# Sequenzer.net
KiCad netlist of a schematic drawn in EAGLE
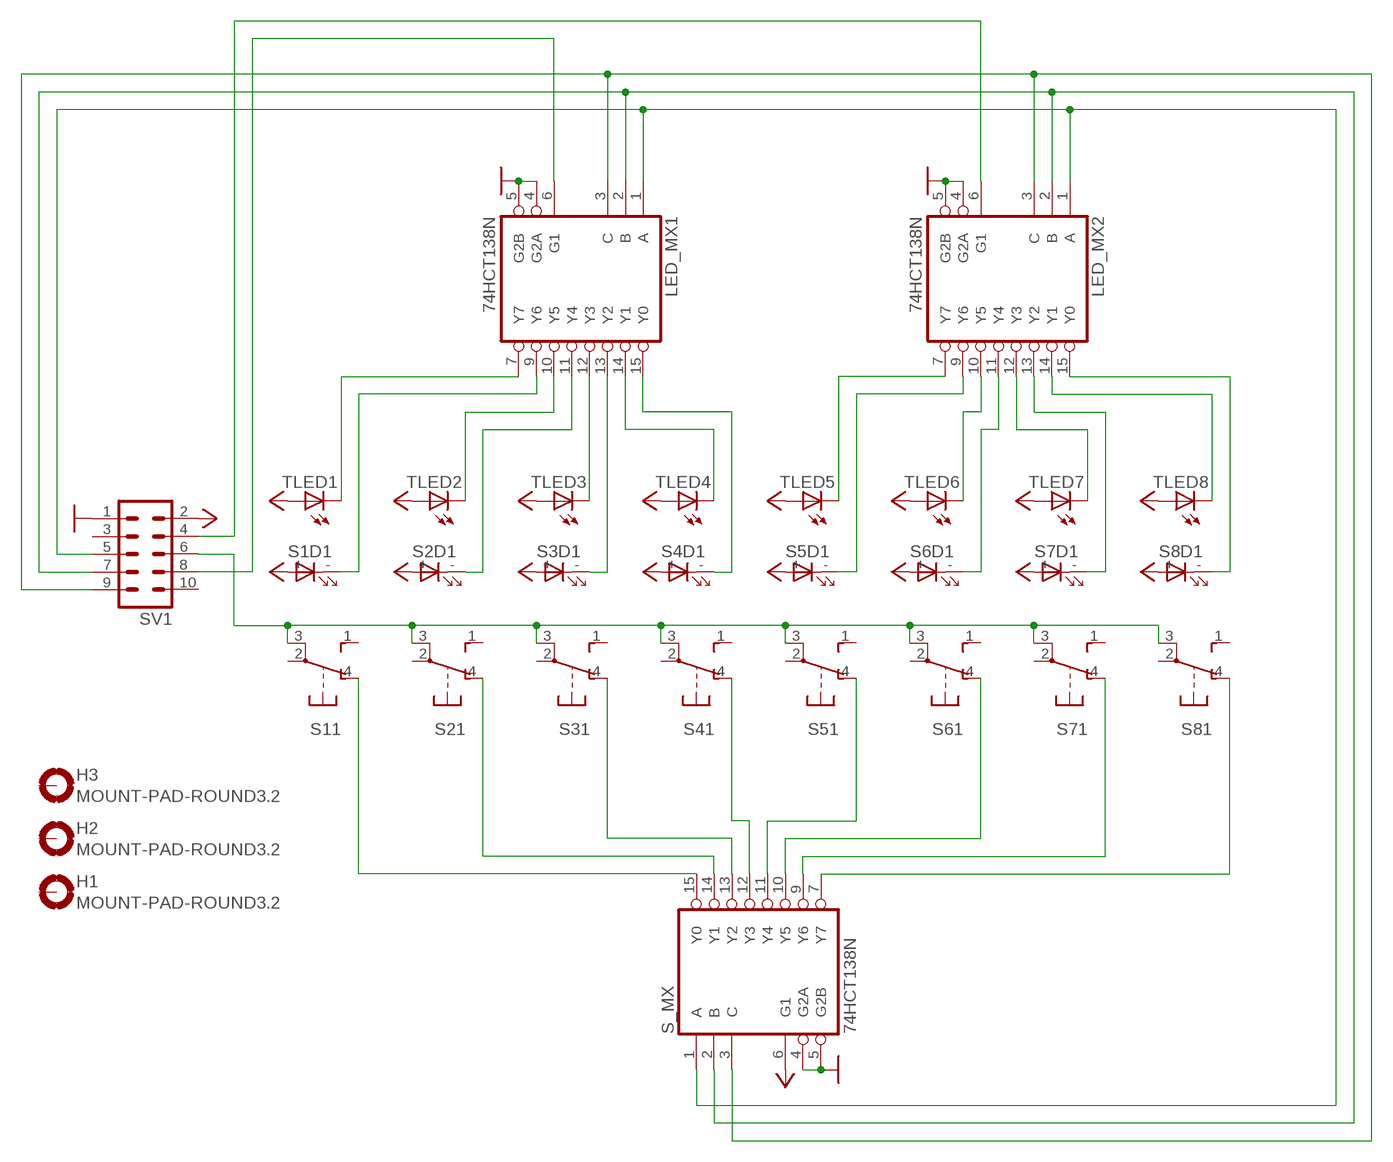
[diagram p0: schematic, sheet 1]

(export (version "E")
  (design (tool "Eeschema 10.0.6"))
  (components
    (comp (ref "H1")
      (value "MOUNT-PAD-ROUND3.2")
      (footprint "eagle-import:3,2-PAD")
      (libsource (lib "eagle-import") (part "MOUNT-PAD-ROUND3.2"))
    )
    (comp (ref "H2")
      (value "MOUNT-PAD-ROUND3.2")
      (footprint "eagle-import:3,2-PAD")
      (libsource (lib "eagle-import") (part "MOUNT-PAD-ROUND3.2"))
    )
    (comp (ref "H3")
      (value "MOUNT-PAD-ROUND3.2")
      (footprint "eagle-import:3,2-PAD")
      (libsource (lib "eagle-import") (part "MOUNT-PAD-ROUND3.2"))
    )
    (comp (ref "LED_MX1")
      (value "74HCT138N")
      (footprint "eagle-import:DIL16")
      (libsource (lib "eagle-import") (part "74138NHCT"))
    )
    (comp (ref "LED_MX2")
      (value "74HCT138N")
      (footprint "eagle-import:DIL16")
      (libsource (lib "eagle-import") (part "74138NHCT"))
    )
    (comp (ref "S1")
      (value "SRKL")
      (footprint "eagle-import:SRKL")
      (libsource (lib "eagle-import") (part "SRKL"))
    )
    (comp (ref "S2")
      (value "SRKL")
      (footprint "eagle-import:SRKL")
      (libsource (lib "eagle-import") (part "SRKL"))
    )
    (comp (ref "S3")
      (value "SRKL")
      (footprint "eagle-import:SRKL")
      (libsource (lib "eagle-import") (part "SRKL"))
    )
    (comp (ref "S4")
      (value "SRKL")
      (footprint "eagle-import:SRKL")
      (libsource (lib "eagle-import") (part "SRKL"))
    )
    (comp (ref "S5")
      (value "SRKL")
      (footprint "eagle-import:SRKL")
      (libsource (lib "eagle-import") (part "SRKL"))
    )
    (comp (ref "S6")
      (value "SRKL")
      (footprint "eagle-import:SRKL")
      (libsource (lib "eagle-import") (part "SRKL"))
    )
    (comp (ref "S7")
      (value "SRKL")
      (footprint "eagle-import:SRKL")
      (libsource (lib "eagle-import") (part "SRKL"))
    )
    (comp (ref "S8")
      (value "SRKL")
      (footprint "eagle-import:SRKL")
      (libsource (lib "eagle-import") (part "SRKL"))
    )
    (comp (ref "SV1")
      (value "ML10")
      (footprint "eagle-import:ML10")
      (libsource (lib "eagle-import") (part "ML10"))
    )
    (comp (ref "S_MX")
      (value "74HCT138N")
      (footprint "eagle-import:DIL16")
      (libsource (lib "eagle-import") (part "74138NHCT"))
    )
    (comp (ref "TLED1")
      (value "LED3MM")
      (footprint "eagle-import:LED3MM")
      (libsource (lib "eagle-import") (part "LED3MM"))
    )
    (comp (ref "TLED2")
      (value "LED3MM")
      (footprint "eagle-import:LED3MM")
      (libsource (lib "eagle-import") (part "LED3MM"))
    )
    (comp (ref "TLED3")
      (value "LED3MM")
      (footprint "eagle-import:LED3MM")
      (libsource (lib "eagle-import") (part "LED3MM"))
    )
    (comp (ref "TLED4")
      (value "LED3MM")
      (footprint "eagle-import:LED3MM")
      (libsource (lib "eagle-import") (part "LED3MM"))
    )
    (comp (ref "TLED5")
      (value "LED3MM")
      (footprint "eagle-import:LED3MM")
      (libsource (lib "eagle-import") (part "LED3MM"))
    )
    (comp (ref "TLED6")
      (value "LED3MM")
      (footprint "eagle-import:LED3MM")
      (libsource (lib "eagle-import") (part "LED3MM"))
    )
    (comp (ref "TLED7")
      (value "LED3MM")
      (footprint "eagle-import:LED3MM")
      (libsource (lib "eagle-import") (part "LED3MM"))
    )
    (comp (ref "TLED8")
      (value "LED3MM")
      (footprint "eagle-import:LED3MM")
      (libsource (lib "eagle-import") (part "LED3MM"))
    )
  )
  (nets
    (net (code "1") (name "GND") (class "Default")
      (node (ref "LED_MX1") (pin "4") (pinfunction "G2A_4") (pintype "input"))
      (node (ref "LED_MX1") (pin "5") (pinfunction "G2B_5") (pintype "input"))
      (node (ref "LED_MX2") (pin "4") (pinfunction "G2A_4") (pintype "input"))
      (node (ref "LED_MX2") (pin "5") (pinfunction "G2B_5") (pintype "input"))
      (node (ref "SV1") (pin "1") (pinfunction "1_1") (pintype "passive"))
      (node (ref "S_MX") (pin "4") (pinfunction "G2A_4") (pintype "input"))
      (node (ref "S_MX") (pin "5") (pinfunction "G2B_5") (pintype "input"))
    )
    (net (code "2") (name "Net-(LED_MX1A-A)") (class "Default")
      (node (ref "LED_MX1") (pin "1") (pinfunction "A_1") (pintype "input"))
      (node (ref "LED_MX2") (pin "1") (pinfunction "A_1") (pintype "input"))
      (node (ref "SV1") (pin "5") (pinfunction "5_5") (pintype "passive"))
      (node (ref "S_MX") (pin "1") (pinfunction "A_1") (pintype "input"))
    )
    (net (code "3") (name "Net-(LED_MX1A-B)") (class "Default")
      (node (ref "LED_MX1") (pin "2") (pinfunction "B_2") (pintype "input"))
      (node (ref "LED_MX2") (pin "2") (pinfunction "B_2") (pintype "input"))
      (node (ref "SV1") (pin "7") (pinfunction "7_7") (pintype "passive"))
      (node (ref "S_MX") (pin "2") (pinfunction "B_2") (pintype "input"))
    )
    (net (code "4") (name "Net-(LED_MX1A-C)") (class "Default")
      (node (ref "LED_MX1") (pin "3") (pinfunction "C_3") (pintype "input"))
      (node (ref "LED_MX2") (pin "3") (pinfunction "C_3") (pintype "input"))
      (node (ref "SV1") (pin "9") (pinfunction "9_9") (pintype "passive"))
      (node (ref "S_MX") (pin "3") (pinfunction "C_3") (pintype "input"))
    )
    (net (code "5") (name "Net-(LED_MX1A-G1)") (class "Default")
      (node (ref "LED_MX1") (pin "6") (pinfunction "G1_6") (pintype "input"))
      (node (ref "SV1") (pin "8") (pinfunction "8_8") (pintype "passive"))
    )
    (net (code "6") (name "Net-(LED_MX1A-Y0)") (class "Default")
      (node (ref "LED_MX1") (pin "15") (pinfunction "Y0_15") (pintype "output"))
      (node (ref "S4") (pin "-") (pinfunction "C_-") (pintype "passive"))
    )
    (net (code "7") (name "Net-(LED_MX1A-Y1)") (class "Default")
      (node (ref "LED_MX1") (pin "14") (pinfunction "Y1_14") (pintype "output"))
      (node (ref "TLED4") (pin "K") (pinfunction "C_K") (pintype "passive"))
    )
    (net (code "8") (name "Net-(LED_MX1A-Y2)") (class "Default")
      (node (ref "LED_MX1") (pin "13") (pinfunction "Y2_13") (pintype "output"))
      (node (ref "S3") (pin "-") (pinfunction "C_-") (pintype "passive"))
    )
    (net (code "9") (name "Net-(LED_MX1A-Y3)") (class "Default")
      (node (ref "LED_MX1") (pin "12") (pinfunction "Y3_12") (pintype "output"))
      (node (ref "TLED3") (pin "K") (pinfunction "C_K") (pintype "passive"))
    )
    (net (code "10") (name "Net-(LED_MX1A-Y4)") (class "Default")
      (node (ref "LED_MX1") (pin "11") (pinfunction "Y4_11") (pintype "output"))
      (node (ref "S2") (pin "-") (pinfunction "C_-") (pintype "passive"))
    )
    (net (code "11") (name "Net-(LED_MX1A-Y5)") (class "Default")
      (node (ref "LED_MX1") (pin "10") (pinfunction "Y5_10") (pintype "output"))
      (node (ref "TLED2") (pin "K") (pinfunction "C_K") (pintype "passive"))
    )
    (net (code "12") (name "Net-(LED_MX1A-Y6)") (class "Default")
      (node (ref "LED_MX1") (pin "9") (pinfunction "Y6_9") (pintype "output"))
      (node (ref "S1") (pin "-") (pinfunction "C_-") (pintype "passive"))
    )
    (net (code "13") (name "Net-(LED_MX1A-Y7)") (class "Default")
      (node (ref "LED_MX1") (pin "7") (pinfunction "Y7_7") (pintype "output"))
      (node (ref "TLED1") (pin "K") (pinfunction "C_K") (pintype "passive"))
    )
    (net (code "14") (name "Net-(LED_MX2A-G1)") (class "Default")
      (node (ref "LED_MX2") (pin "6") (pinfunction "G1_6") (pintype "input"))
      (node (ref "SV1") (pin "4") (pinfunction "4_4") (pintype "passive"))
    )
    (net (code "15") (name "Net-(LED_MX2A-Y0)") (class "Default")
      (node (ref "LED_MX2") (pin "15") (pinfunction "Y0_15") (pintype "output"))
      (node (ref "S8") (pin "-") (pinfunction "C_-") (pintype "passive"))
    )
    (net (code "16") (name "Net-(LED_MX2A-Y1)") (class "Default")
      (node (ref "LED_MX2") (pin "14") (pinfunction "Y1_14") (pintype "output"))
      (node (ref "TLED8") (pin "K") (pinfunction "C_K") (pintype "passive"))
    )
    (net (code "17") (name "Net-(LED_MX2A-Y2)") (class "Default")
      (node (ref "LED_MX2") (pin "13") (pinfunction "Y2_13") (pintype "output"))
      (node (ref "S7") (pin "-") (pinfunction "C_-") (pintype "passive"))
    )
    (net (code "18") (name "Net-(LED_MX2A-Y3)") (class "Default")
      (node (ref "LED_MX2") (pin "12") (pinfunction "Y3_12") (pintype "output"))
      (node (ref "TLED7") (pin "K") (pinfunction "C_K") (pintype "passive"))
    )
    (net (code "19") (name "Net-(LED_MX2A-Y4)") (class "Default")
      (node (ref "LED_MX2") (pin "11") (pinfunction "Y4_11") (pintype "output"))
      (node (ref "S6") (pin "-") (pinfunction "C_-") (pintype "passive"))
    )
    (net (code "20") (name "Net-(LED_MX2A-Y5)") (class "Default")
      (node (ref "LED_MX2") (pin "10") (pinfunction "Y5_10") (pintype "output"))
      (node (ref "TLED6") (pin "K") (pinfunction "C_K") (pintype "passive"))
    )
    (net (code "21") (name "Net-(LED_MX2A-Y6)") (class "Default")
      (node (ref "LED_MX2") (pin "9") (pinfunction "Y6_9") (pintype "output"))
      (node (ref "S5") (pin "-") (pinfunction "C_-") (pintype "passive"))
    )
    (net (code "22") (name "Net-(LED_MX2A-Y7)") (class "Default")
      (node (ref "LED_MX2") (pin "7") (pinfunction "Y7_7") (pintype "output"))
      (node (ref "TLED5") (pin "K") (pinfunction "C_K") (pintype "passive"))
    )
    (net (code "23") (name "Net-(S1A-O)") (class "Default")
      (node (ref "S1") (pin "4") (pinfunction "O_4") (pintype "passive"))
      (node (ref "S_MX") (pin "15") (pinfunction "Y0_15") (pintype "output"))
    )
    (net (code "24") (name "Net-(S1A-P-Pad3)") (class "Default")
      (node (ref "S1") (pin "3") (pinfunction "P_3") (pintype "passive"))
      (node (ref "S2") (pin "3") (pinfunction "P_3") (pintype "passive"))
      (node (ref "S3") (pin "3") (pinfunction "P_3") (pintype "passive"))
      (node (ref "S4") (pin "3") (pinfunction "P_3") (pintype "passive"))
      (node (ref "S5") (pin "3") (pinfunction "P_3") (pintype "passive"))
      (node (ref "S6") (pin "3") (pinfunction "P_3") (pintype "passive"))
      (node (ref "S7") (pin "3") (pinfunction "P_3") (pintype "passive"))
      (node (ref "S8") (pin "3") (pinfunction "P_3") (pintype "passive"))
      (node (ref "SV1") (pin "6") (pinfunction "6_6") (pintype "passive"))
    )
    (net (code "25") (name "Net-(S2A-O)") (class "Default")
      (node (ref "S2") (pin "4") (pinfunction "O_4") (pintype "passive"))
      (node (ref "S_MX") (pin "14") (pinfunction "Y1_14") (pintype "output"))
    )
    (net (code "26") (name "Net-(S3A-O)") (class "Default")
      (node (ref "S3") (pin "4") (pinfunction "O_4") (pintype "passive"))
      (node (ref "S_MX") (pin "13") (pinfunction "Y2_13") (pintype "output"))
    )
    (net (code "27") (name "Net-(S4A-O)") (class "Default")
      (node (ref "S4") (pin "4") (pinfunction "O_4") (pintype "passive"))
      (node (ref "S_MX") (pin "12") (pinfunction "Y3_12") (pintype "output"))
    )
    (net (code "28") (name "Net-(S5A-O)") (class "Default")
      (node (ref "S5") (pin "4") (pinfunction "O_4") (pintype "passive"))
      (node (ref "S_MX") (pin "11") (pinfunction "Y4_11") (pintype "output"))
    )
    (net (code "29") (name "Net-(S6A-O)") (class "Default")
      (node (ref "S6") (pin "4") (pinfunction "O_4") (pintype "passive"))
      (node (ref "S_MX") (pin "10") (pinfunction "Y5_10") (pintype "output"))
    )
    (net (code "30") (name "Net-(S7A-O)") (class "Default")
      (node (ref "S7") (pin "4") (pinfunction "O_4") (pintype "passive"))
      (node (ref "S_MX") (pin "9") (pinfunction "Y6_9") (pintype "output"))
    )
    (net (code "31") (name "Net-(S8A-O)") (class "Default")
      (node (ref "S8") (pin "4") (pinfunction "O_4") (pintype "passive"))
      (node (ref "S_MX") (pin "7") (pinfunction "Y7_7") (pintype "output"))
    )
    (net (code "32") (name "VCC") (class "Default")
      (node (ref "S1") (pin "+") (pinfunction "A_+") (pintype "passive"))
      (node (ref "S2") (pin "+") (pinfunction "A_+") (pintype "passive"))
      (node (ref "S3") (pin "+") (pinfunction "A_+") (pintype "passive"))
      (node (ref "S4") (pin "+") (pinfunction "A_+") (pintype "passive"))
      (node (ref "S5") (pin "+") (pinfunction "A_+") (pintype "passive"))
      (node (ref "S6") (pin "+") (pinfunction "A_+") (pintype "passive"))
      (node (ref "S7") (pin "+") (pinfunction "A_+") (pintype "passive"))
      (node (ref "S8") (pin "+") (pinfunction "A_+") (pintype "passive"))
      (node (ref "SV1") (pin "2") (pinfunction "2_2") (pintype "passive"))
      (node (ref "S_MX") (pin "6") (pinfunction "G1_6") (pintype "input"))
      (node (ref "TLED1") (pin "A") (pinfunction "A_A") (pintype "passive"))
      (node (ref "TLED2") (pin "A") (pinfunction "A_A") (pintype "passive"))
      (node (ref "TLED3") (pin "A") (pinfunction "A_A") (pintype "passive"))
      (node (ref "TLED4") (pin "A") (pinfunction "A_A") (pintype "passive"))
      (node (ref "TLED5") (pin "A") (pinfunction "A_A") (pintype "passive"))
      (node (ref "TLED6") (pin "A") (pinfunction "A_A") (pintype "passive"))
      (node (ref "TLED7") (pin "A") (pinfunction "A_A") (pintype "passive"))
      (node (ref "TLED8") (pin "A") (pinfunction "A_A") (pintype "passive"))
    )
    (net (code "33") (name "unconnected-(H1-MOUNT-PadB3,2)") (class "Default")
      (node (ref "H1") (pin "B3,2") (pinfunction "MOUNT_B3,2") (pintype "passive"))
    )
    (net (code "34") (name "unconnected-(H2-MOUNT-PadB3,2)") (class "Default")
      (node (ref "H2") (pin "B3,2") (pinfunction "MOUNT_B3,2") (pintype "passive"))
    )
    (net (code "35") (name "unconnected-(H3-MOUNT-PadB3,2)") (class "Default")
      (node (ref "H3") (pin "B3,2") (pinfunction "MOUNT_B3,2") (pintype "passive"))
    )
    (net (code "36") (name "unconnected-(S1A-P-Pad2)") (class "Default")
      (node (ref "S1") (pin "2") (pinfunction "P_2") (pintype "passive"))
    )
    (net (code "37") (name "unconnected-(S1A-S-Pad1)") (class "Default")
      (node (ref "S1") (pin "1") (pinfunction "S_1") (pintype "passive"))
    )
    (net (code "38") (name "unconnected-(S2A-P-Pad2)") (class "Default")
      (node (ref "S2") (pin "2") (pinfunction "P_2") (pintype "passive"))
    )
    (net (code "39") (name "unconnected-(S2A-S-Pad1)") (class "Default")
      (node (ref "S2") (pin "1") (pinfunction "S_1") (pintype "passive"))
    )
    (net (code "40") (name "unconnected-(S3A-P-Pad2)") (class "Default")
      (node (ref "S3") (pin "2") (pinfunction "P_2") (pintype "passive"))
    )
    (net (code "41") (name "unconnected-(S3A-S-Pad1)") (class "Default")
      (node (ref "S3") (pin "1") (pinfunction "S_1") (pintype "passive"))
    )
    (net (code "42") (name "unconnected-(S4A-P-Pad2)") (class "Default")
      (node (ref "S4") (pin "2") (pinfunction "P_2") (pintype "passive"))
    )
    (net (code "43") (name "unconnected-(S4A-S-Pad1)") (class "Default")
      (node (ref "S4") (pin "1") (pinfunction "S_1") (pintype "passive"))
    )
    (net (code "44") (name "unconnected-(S5A-P-Pad2)") (class "Default")
      (node (ref "S5") (pin "2") (pinfunction "P_2") (pintype "passive"))
    )
    (net (code "45") (name "unconnected-(S5A-S-Pad1)") (class "Default")
      (node (ref "S5") (pin "1") (pinfunction "S_1") (pintype "passive"))
    )
    (net (code "46") (name "unconnected-(S6A-P-Pad2)") (class "Default")
      (node (ref "S6") (pin "2") (pinfunction "P_2") (pintype "passive"))
    )
    (net (code "47") (name "unconnected-(S6A-S-Pad1)") (class "Default")
      (node (ref "S6") (pin "1") (pinfunction "S_1") (pintype "passive"))
    )
    (net (code "48") (name "unconnected-(S7A-P-Pad2)") (class "Default")
      (node (ref "S7") (pin "2") (pinfunction "P_2") (pintype "passive"))
    )
    (net (code "49") (name "unconnected-(S7A-S-Pad1)") (class "Default")
      (node (ref "S7") (pin "1") (pinfunction "S_1") (pintype "passive"))
    )
    (net (code "50") (name "unconnected-(S8A-P-Pad2)") (class "Default")
      (node (ref "S8") (pin "2") (pinfunction "P_2") (pintype "passive"))
    )
    (net (code "51") (name "unconnected-(S8A-S-Pad1)") (class "Default")
      (node (ref "S8") (pin "1") (pinfunction "S_1") (pintype "passive"))
    )
    (net (code "52") (name "unconnected-(SV1-Pad3)") (class "Default")
      (node (ref "SV1") (pin "3") (pinfunction "3_3") (pintype "passive"))
    )
    (net (code "53") (name "unconnected-(SV1-Pad10)") (class "Default")
      (node (ref "SV1") (pin "10") (pinfunction "10_10") (pintype "passive"))
    )
  )
)
